# Artemis-Flex-Femto.net
KiCad netlist of a schematic drawn in EAGLE
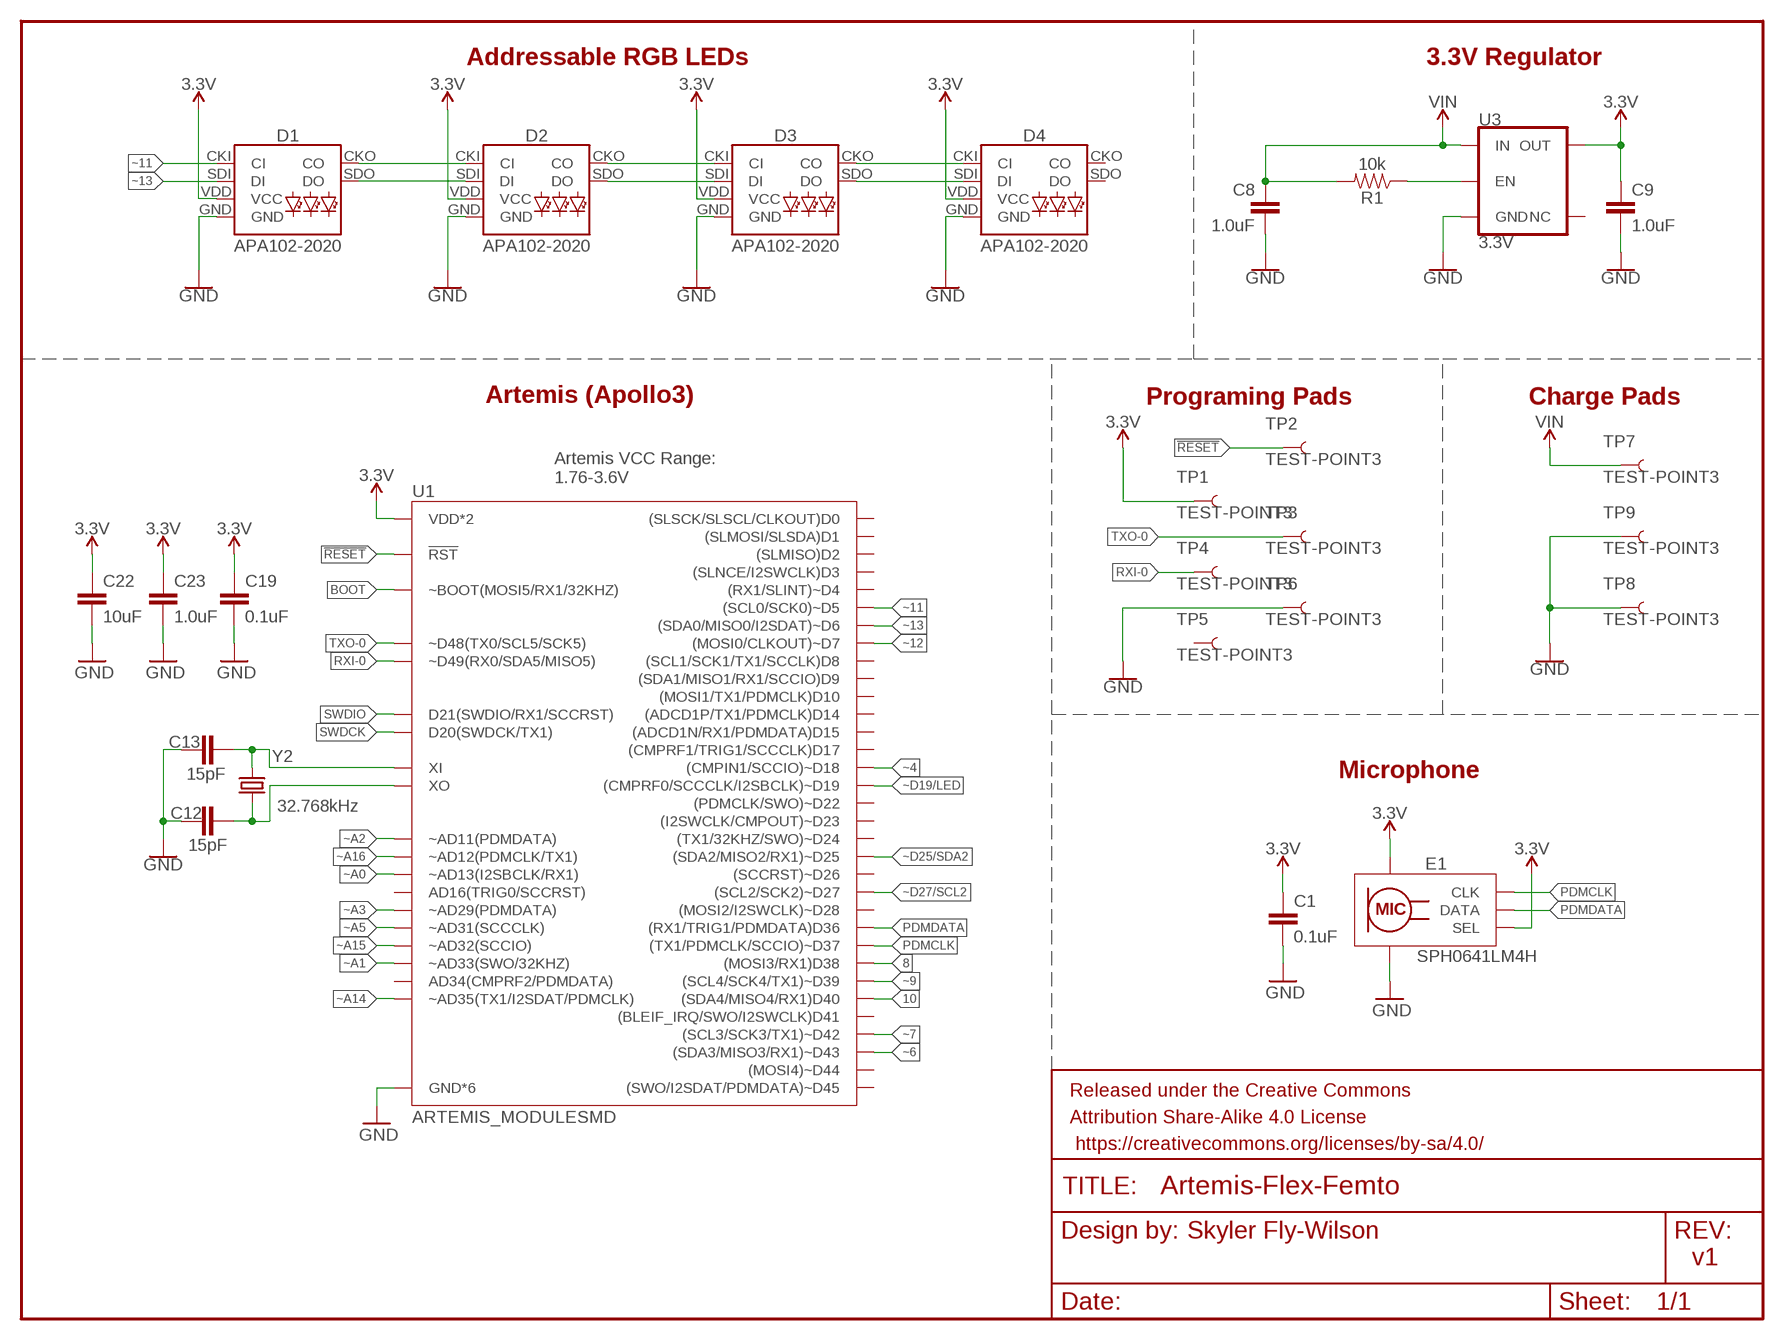
[diagram p0: schematic, sheet 1]

(export (version "E")
  (design (tool "Eeschema 10.0.6"))
  (components
    (comp (ref "C1")
      (value "0.1uF")
      (footprint "eagle-import:0402-TIGHT")
      (libsource (lib "eagle-import") (part "0.1UF-0402T-16V-10%"))
    )
    (comp (ref "C8")
      (value "1.0uF")
      (footprint "eagle-import:0402-TIGHT")
      (libsource (lib "eagle-import") (part "1.0UF-0402T-16V-10%"))
    )
    (comp (ref "C9")
      (value "1.0uF")
      (footprint "eagle-import:0402-TIGHT")
      (libsource (lib "eagle-import") (part "1.0UF-0402T-16V-10%"))
    )
    (comp (ref "C12")
      (value "15pF")
      (footprint "eagle-import:0603")
      (libsource (lib "eagle-import") (part "15PF-0603-50V-5%"))
    )
    (comp (ref "C13")
      (value "15pF")
      (footprint "eagle-import:0603")
      (libsource (lib "eagle-import") (part "15PF-0603-50V-5%"))
    )
    (comp (ref "C19")
      (value "0.1uF")
      (footprint "eagle-import:0402-TIGHT")
      (libsource (lib "eagle-import") (part "0.1UF-0402T-16V-10%"))
    )
    (comp (ref "C22")
      (value "10uF")
      (footprint "eagle-import:0603")
      (libsource (lib "eagle-import") (part "10UF-0603-6.3V-20%"))
    )
    (comp (ref "C23")
      (value "1.0uF")
      (footprint "eagle-import:0402-TIGHT")
      (libsource (lib "eagle-import") (part "1.0UF-0402T-16V-10%"))
    )
    (comp (ref "D1")
      (value "APA102-2020")
      (footprint "eagle-import:APA102-2020")
      (libsource (lib "eagle-import") (part "APA102-2020"))
    )
    (comp (ref "D2")
      (value "APA102-2020")
      (footprint "eagle-import:APA102-2020")
      (libsource (lib "eagle-import") (part "APA102-2020"))
    )
    (comp (ref "D3")
      (value "APA102-2020")
      (footprint "eagle-import:APA102-2020")
      (libsource (lib "eagle-import") (part "APA102-2020"))
    )
    (comp (ref "D4")
      (value "APA102-2020")
      (footprint "eagle-import:APA102-2020")
      (libsource (lib "eagle-import") (part "APA102-2020"))
    )
    (comp (ref "E1")
      (value "SPH0641LM4H")
      (footprint "eagle-import:SPH0641LM4H-1_MICROPHONE")
      (libsource (lib "eagle-import") (part "SPH0641LM4H-1_MICROPHONE"))
    )
    (comp (ref "FRAME1")
      (value "FRAME-LETTER")
      (footprint "eagle-import:CREATIVE_COMMONS")
      (libsource (lib "eagle-import") (part "FRAME-LETTER"))
    )
    (comp (ref "R1")
      (value "10k")
      (footprint "eagle-import:0603")
      (libsource (lib "eagle-import") (part "10KOHM-0603-1/10W-1%"))
    )
    (comp (ref "TP1")
      (value "TEST-POINT3")
      (footprint "eagle-import:PAD.03X.03")
      (libsource (lib "eagle-import") (part "TEST-POINT3"))
    )
    (comp (ref "TP2")
      (value "TEST-POINT3")
      (footprint "eagle-import:PAD.03X.03")
      (libsource (lib "eagle-import") (part "TEST-POINT3"))
    )
    (comp (ref "TP3")
      (value "TEST-POINT3")
      (footprint "eagle-import:PAD.03X.03")
      (libsource (lib "eagle-import") (part "TEST-POINT3"))
    )
    (comp (ref "TP4")
      (value "TEST-POINT3")
      (footprint "eagle-import:PAD.03X.03")
      (libsource (lib "eagle-import") (part "TEST-POINT3"))
    )
    (comp (ref "TP5")
      (value "TEST-POINT3")
      (footprint "eagle-import:PAD.03X.03")
      (libsource (lib "eagle-import") (part "TEST-POINT3"))
    )
    (comp (ref "TP6")
      (value "TEST-POINT3")
      (footprint "eagle-import:PAD.03X.03")
      (libsource (lib "eagle-import") (part "TEST-POINT3"))
    )
    (comp (ref "TP7")
      (value "TEST-POINT3")
      (footprint "eagle-import:PAD.03X.03")
      (libsource (lib "eagle-import") (part "TEST-POINT3"))
    )
    (comp (ref "TP8")
      (value "TEST-POINT3")
      (footprint "eagle-import:PAD.03X.03")
      (libsource (lib "eagle-import") (part "TEST-POINT3"))
    )
    (comp (ref "TP9")
      (value "TEST-POINT3")
      (footprint "eagle-import:PAD.03X.03")
      (libsource (lib "eagle-import") (part "TEST-POINT3"))
    )
    (comp (ref "U1")
      (value "ARTEMIS_MODULESMD")
      (footprint "eagle-import:ARTEMIS_FP")
      (libsource (lib "eagle-import") (part "ARTEMIS_MODULESMD"))
    )
    (comp (ref "U3")
      (value "3.3V")
      (footprint "eagle-import:SOT23-5")
      (libsource (lib "eagle-import") (part "V_REG_AP2112K-3.3V"))
    )
    (comp (ref "Y2")
      (value "32.768kHz")
      (footprint "eagle-import:CRYSTAL-SMD-3.2X1.5MM")
      (libsource (lib "eagle-import") (part "CRYSTAL-32.768KHZSMD-3.2X1.5"))
    )
  )
  (nets
    (net (code "1") (name "/~{4}") (class "Default")
      (node (ref "U1") (pin "~D18") (pinfunction "(CMPIN1/SCCIO)~{D18}_~D18") (pintype "bidirectional"))
    )
    (net (code "2") (name "/~{6}") (class "Default")
      (node (ref "U1") (pin "~D43") (pinfunction "(SDA3/MISO3/RX1)~{D43}_~D43") (pintype "bidirectional"))
    )
    (net (code "3") (name "/~{7}") (class "Default")
      (node (ref "U1") (pin "~D42") (pinfunction "(SCL3/SCK3/TX1)~{D42}_~D42") (pintype "bidirectional"))
    )
    (net (code "4") (name "/~{9}") (class "Default")
      (node (ref "U1") (pin "~D39") (pinfunction "(SCL4/SCK4/TX1)~{D39}_~D39") (pintype "bidirectional"))
    )
    (net (code "5") (name "/~{11}") (class "Default")
      (node (ref "U1") (pin "~D5") (pinfunction "(SCL0/SCK0)~{D5}_~D5") (pintype "bidirectional"))
    )
    (net (code "6") (name "/~{12}") (class "Default")
      (node (ref "U1") (pin "D7") (pinfunction "(MOSI0/CLKOUT)~{D7}_D7") (pintype "bidirectional"))
    )
    (net (code "7") (name "/~{13}") (class "Default")
      (node (ref "U1") (pin "~D6") (pinfunction "(SDA0/MISO0/I2SDAT)~{D6}_~D6") (pintype "bidirectional"))
    )
    (net (code "8") (name "/~{A0}") (class "Default")
      (node (ref "U1") (pin "~AD13") (pinfunction "~{AD13(I2SBCLK/RX1})_~AD13") (pintype "bidirectional"))
    )
    (net (code "9") (name "/~{A1}") (class "Default")
      (node (ref "U1") (pin "~AD33/SWO") (pinfunction "~{AD33(SWO/32KHZ})_~AD33/SWO") (pintype "bidirectional"))
    )
    (net (code "10") (name "/~{A2}") (class "Default")
      (node (ref "U1") (pin "~AD11") (pinfunction "~{AD11(PDMDATA})_~AD11") (pintype "bidirectional"))
    )
    (net (code "11") (name "/~{A3}") (class "Default")
      (node (ref "U1") (pin "~AD29") (pinfunction "~{AD29(PDMDATA})_~AD29") (pintype "bidirectional"))
    )
    (net (code "12") (name "/~{A5}") (class "Default")
      (node (ref "U1") (pin "~AD31") (pinfunction "~{AD31(SCCCLK})_~AD31") (pintype "bidirectional"))
    )
    (net (code "13") (name "/~{A14}") (class "Default")
      (node (ref "U1") (pin "~AD35") (pinfunction "~{AD35(TX1/I2SDAT/PDMCLK})_~AD35") (pintype "bidirectional"))
    )
    (net (code "14") (name "/~{A15}") (class "Default")
      (node (ref "U1") (pin "~AD32") (pinfunction "~{AD32(SCCIO})_~AD32") (pintype "bidirectional"))
    )
    (net (code "15") (name "/~{A16}") (class "Default")
      (node (ref "U1") (pin "~AD12") (pinfunction "~{AD12(PDMCLK/TX1})_~AD12") (pintype "bidirectional"))
    )
    (net (code "16") (name "/~{D19{slash}LED}") (class "Default")
      (node (ref "U1") (pin "~D19") (pinfunction "(CMPRF0/SCCCLK/I2SBCLK)~{D19}_~D19") (pintype "bidirectional"))
    )
    (net (code "17") (name "/~{D25{slash}SDA2}") (class "Default")
      (node (ref "U1") (pin "~D25") (pinfunction "(SDA2/MISO2/RX1)~{D25}_~D25") (pintype "bidirectional"))
    )
    (net (code "18") (name "/~{D27{slash}SCL2}") (class "Default")
      (node (ref "U1") (pin "~D27") (pinfunction "(SCL2/SCK2)~{D27}_~D27") (pintype "bidirectional"))
    )
    (net (code "19") (name "/~{RESET}") (class "Default")
      (node (ref "U1") (pin "~RST") (pinfunction "~{RST}_~RST") (pintype "bidirectional"))
    )
    (net (code "20") (name "3.3V") (class "Default")
      (node (ref "C1") (pin "1") (pinfunction "1_1") (pintype "passive"))
      (node (ref "C19") (pin "2") (pinfunction "2_2") (pintype "passive"))
      (node (ref "C22") (pin "1") (pinfunction "1_1") (pintype "passive"))
      (node (ref "C23") (pin "1") (pinfunction "1_1") (pintype "passive"))
      (node (ref "C9") (pin "1") (pinfunction "1_1") (pintype "passive"))
      (node (ref "D1") (pin "VDD") (pinfunction "VCC_VDD") (pintype "bidirectional"))
      (node (ref "D2") (pin "VDD") (pinfunction "VCC_VDD") (pintype "bidirectional"))
      (node (ref "D3") (pin "VDD") (pinfunction "VCC_VDD") (pintype "bidirectional"))
      (node (ref "D4") (pin "VDD") (pinfunction "VCC_VDD") (pintype "bidirectional"))
      (node (ref "E1") (pin "2") (pinfunction "SEL_2") (pintype "input"))
      (node (ref "E1") (pin "5") (pinfunction "VDD_5") (pintype "power_in"))
      (node (ref "TP1") (pin "P$1") (pinfunction "1_P$1") (pintype "bidirectional"))
      (node (ref "U1") (pin "VDD@36") (pinfunction "VDD*2_VDD@36") (pintype "bidirectional"))
      (node (ref "U1") (pin "VDD@37") (pinfunction "VDD*2_VDD@37") (pintype "bidirectional"))
      (node (ref "U3") (pin "5") (pinfunction "OUT_5") (pintype "passive"))
    )
    (net (code "21") (name "8") (class "Default")
      (node (ref "U1") (pin "D38") (pinfunction "(MOSI3/RX1)D38_D38") (pintype "bidirectional"))
    )
    (net (code "22") (name "10") (class "Default")
      (node (ref "U1") (pin "D40") (pinfunction "(SDA4/MISO4/RX1)D40_D40") (pintype "bidirectional"))
    )
    (net (code "23") (name "BOOT") (class "Default")
      (node (ref "U1") (pin "BOOT") (pinfunction "~{BOOT(MOSI5/RX1/32KHZ})_BOOT") (pintype "bidirectional"))
    )
    (net (code "24") (name "GND") (class "Default")
      (node (ref "C1") (pin "2") (pinfunction "2_2") (pintype "passive"))
      (node (ref "C12") (pin "1") (pinfunction "1_1") (pintype "passive"))
      (node (ref "C13") (pin "1") (pinfunction "1_1") (pintype "passive"))
      (node (ref "C19") (pin "1") (pinfunction "1_1") (pintype "passive"))
      (node (ref "C22") (pin "2") (pinfunction "2_2") (pintype "passive"))
      (node (ref "C23") (pin "2") (pinfunction "2_2") (pintype "passive"))
      (node (ref "C8") (pin "2") (pinfunction "2_2") (pintype "passive"))
      (node (ref "C9") (pin "2") (pinfunction "2_2") (pintype "passive"))
      (node (ref "D1") (pin "GND") (pinfunction "GND_GND") (pintype "bidirectional"))
      (node (ref "D2") (pin "GND") (pinfunction "GND_GND") (pintype "bidirectional"))
      (node (ref "D3") (pin "GND") (pinfunction "GND_GND") (pintype "bidirectional"))
      (node (ref "D4") (pin "GND") (pinfunction "GND_GND") (pintype "bidirectional"))
      (node (ref "E1") (pin "3") (pinfunction "GND_3") (pintype "power_in"))
      (node (ref "E1") (pin "6") (pinfunction "GND_6") (pintype "power_in"))
      (node (ref "E1") (pin "7") (pinfunction "GND_7") (pintype "power_in"))
      (node (ref "E1") (pin "8") (pinfunction "GND_8") (pintype "power_in"))
      (node (ref "TP6") (pin "P$1") (pinfunction "1_P$1") (pintype "bidirectional"))
      (node (ref "TP8") (pin "P$1") (pinfunction "1_P$1") (pintype "bidirectional"))
      (node (ref "TP9") (pin "P$1") (pinfunction "1_P$1") (pintype "bidirectional"))
      (node (ref "U1") (pin "GND@1") (pinfunction "GND*6_GND@1") (pintype "bidirectional"))
      (node (ref "U1") (pin "GND@22") (pinfunction "GND*6_GND@22") (pintype "bidirectional"))
      (node (ref "U1") (pin "GND@38") (pinfunction "GND*6_GND@38") (pintype "bidirectional"))
      (node (ref "U1") (pin "GND@39") (pinfunction "GND*6_GND@39") (pintype "bidirectional"))
      (node (ref "U1") (pin "GND@47") (pinfunction "GND*6_GND@47") (pintype "bidirectional"))
      (node (ref "U1") (pin "GND@59") (pinfunction "GND*6_GND@59") (pintype "bidirectional"))
      (node (ref "U3") (pin "2") (pinfunction "GND_2") (pintype "input"))
    )
    (net (code "25") (name "Net-(D1-CO)") (class "Default")
      (node (ref "D1") (pin "CKO") (pinfunction "CO_CKO") (pintype "bidirectional"))
      (node (ref "D2") (pin "CKI") (pinfunction "CI_CKI") (pintype "bidirectional"))
    )
    (net (code "26") (name "Net-(D1-DO)") (class "Default")
      (node (ref "D1") (pin "SDO") (pinfunction "DO_SDO") (pintype "bidirectional"))
      (node (ref "D2") (pin "SDI") (pinfunction "DI_SDI") (pintype "bidirectional"))
    )
    (net (code "27") (name "Net-(D2-CO)") (class "Default")
      (node (ref "D2") (pin "CKO") (pinfunction "CO_CKO") (pintype "bidirectional"))
      (node (ref "D3") (pin "CKI") (pinfunction "CI_CKI") (pintype "bidirectional"))
    )
    (net (code "28") (name "Net-(D2-DO)") (class "Default")
      (node (ref "D2") (pin "SDO") (pinfunction "DO_SDO") (pintype "bidirectional"))
      (node (ref "D3") (pin "SDI") (pinfunction "DI_SDI") (pintype "bidirectional"))
    )
    (net (code "29") (name "Net-(D3-CO)") (class "Default")
      (node (ref "D3") (pin "CKO") (pinfunction "CO_CKO") (pintype "bidirectional"))
      (node (ref "D4") (pin "CKI") (pinfunction "CI_CKI") (pintype "bidirectional"))
    )
    (net (code "30") (name "Net-(D3-DO)") (class "Default")
      (node (ref "D3") (pin "SDO") (pinfunction "DO_SDO") (pintype "bidirectional"))
      (node (ref "D4") (pin "SDI") (pinfunction "DI_SDI") (pintype "bidirectional"))
    )
    (net (code "31") (name "Net-(U3-EN)") (class "Default")
      (node (ref "R1") (pin "1") (pinfunction "1_1") (pintype "passive"))
      (node (ref "U3") (pin "3") (pinfunction "EN_3") (pintype "input"))
    )
    (net (code "32") (name "Net-(Y2-1)") (class "Default")
      (node (ref "C13") (pin "2") (pinfunction "2_2") (pintype "passive"))
      (node (ref "U1") (pin "XI") (pinfunction "XI_XI") (pintype "bidirectional"))
      (node (ref "Y2") (pin "P$1") (pinfunction "1_P$1") (pintype "passive"))
    )
    (net (code "33") (name "Net-(Y2-2)") (class "Default")
      (node (ref "C12") (pin "2") (pinfunction "2_2") (pintype "passive"))
      (node (ref "U1") (pin "XO") (pinfunction "XO_XO") (pintype "bidirectional"))
      (node (ref "Y2") (pin "P$2") (pinfunction "2_P$2") (pintype "passive"))
    )
    (net (code "34") (name "PDMCLK") (class "Default")
      (node (ref "E1") (pin "4") (pinfunction "CLK_4") (pintype "input"))
      (node (ref "U1") (pin "~D37") (pinfunction "(TX1/PDMCLK/SCCIO)~{D37}_~D37") (pintype "bidirectional"))
    )
    (net (code "35") (name "PDMDATA") (class "Default")
      (node (ref "E1") (pin "1") (pinfunction "DATA_1") (pintype "output"))
      (node (ref "U1") (pin "D36") (pinfunction "(RX1/TRIG1/PDMDATA)D36_D36") (pintype "bidirectional"))
    )
    (net (code "36") (name "RXI-0") (class "Default")
      (node (ref "U1") (pin "RXI-0") (pinfunction "~{D49(RX0/SDA5/MISO5})_RXI-0") (pintype "bidirectional"))
    )
    (net (code "37") (name "SWDCK") (class "Default")
      (node (ref "U1") (pin "SWDCK") (pinfunction "D20(SWDCK/TX1)_SWDCK") (pintype "bidirectional"))
    )
    (net (code "38") (name "SWDIO") (class "Default")
      (node (ref "U1") (pin "SWDIO") (pinfunction "D21(SWDIO/RX1/SCCRST)_SWDIO") (pintype "bidirectional"))
    )
    (net (code "39") (name "TXO-0") (class "Default")
      (node (ref "U1") (pin "TXO-0") (pinfunction "~{D48(TX0/SCL5/SCK5})_TXO-0") (pintype "bidirectional"))
    )
    (net (code "40") (name "VIN") (class "Default")
      (node (ref "C8") (pin "1") (pinfunction "1_1") (pintype "passive"))
      (node (ref "R1") (pin "2") (pinfunction "2_2") (pintype "passive"))
      (node (ref "TP7") (pin "P$1") (pinfunction "1_P$1") (pintype "bidirectional"))
      (node (ref "U3") (pin "1") (pinfunction "IN_1") (pintype "input"))
    )
    (net (code "41") (name "unconnected-(D1-CI-PadCKI)") (class "Default")
      (node (ref "D1") (pin "CKI") (pinfunction "CI_CKI") (pintype "bidirectional"))
    )
    (net (code "42") (name "unconnected-(D1-DI-PadSDI)") (class "Default")
      (node (ref "D1") (pin "SDI") (pinfunction "DI_SDI") (pintype "bidirectional"))
    )
    (net (code "43") (name "unconnected-(D4-CO-PadCKO)") (class "Default")
      (node (ref "D4") (pin "CKO") (pinfunction "CO_CKO") (pintype "bidirectional"))
    )
    (net (code "44") (name "unconnected-(D4-DO-PadSDO)") (class "Default")
      (node (ref "D4") (pin "SDO") (pinfunction "DO_SDO") (pintype "bidirectional"))
    )
    (net (code "45") (name "unconnected-(TP2-1-PadP$1)") (class "Default")
      (node (ref "TP2") (pin "P$1") (pinfunction "1_P$1") (pintype "bidirectional"))
    )
    (net (code "46") (name "unconnected-(TP3-1-PadP$1)") (class "Default")
      (node (ref "TP3") (pin "P$1") (pinfunction "1_P$1") (pintype "bidirectional"))
    )
    (net (code "47") (name "unconnected-(TP4-1-PadP$1)") (class "Default")
      (node (ref "TP4") (pin "P$1") (pinfunction "1_P$1") (pintype "bidirectional"))
    )
    (net (code "48") (name "unconnected-(TP5-1-PadP$1)") (class "Default")
      (node (ref "TP5") (pin "P$1") (pinfunction "1_P$1") (pintype "bidirectional"))
    )
    (net (code "49") (name "unconnected-(U1-(ADCD1N{slash}RX1{slash}PDMDATA)D15-PadD15)") (class "Default")
      (node (ref "U1") (pin "D15") (pinfunction "(ADCD1N/RX1/PDMDATA)D15_D15") (pintype "bidirectional"))
    )
    (net (code "50") (name "unconnected-(U1-(ADCD1P{slash}TX1{slash}PDMCLK)D14-PadD14)") (class "Default")
      (node (ref "U1") (pin "D14") (pinfunction "(ADCD1P/TX1/PDMCLK)D14_D14") (pintype "bidirectional"))
    )
    (net (code "51") (name "unconnected-(U1-(BLEIF_IRQ{slash}SWO{slash}I2SWCLK)D41-PadD41)") (class "Default")
      (node (ref "U1") (pin "D41") (pinfunction "(BLEIF_IRQ/SWO/I2SWCLK)D41_D41") (pintype "bidirectional"))
    )
    (net (code "52") (name "unconnected-(U1-(CMPRF1{slash}TRIG1{slash}SCCCLK)D17-PadD17)") (class "Default")
      (node (ref "U1") (pin "D17") (pinfunction "(CMPRF1/TRIG1/SCCCLK)D17_D17") (pintype "bidirectional"))
    )
    (net (code "53") (name "unconnected-(U1-(I2SWCLK{slash}CMPOUT)~{D23}-Pad~D23)") (class "Default")
      (node (ref "U1") (pin "~D23") (pinfunction "(I2SWCLK/CMPOUT)~{D23}_~D23") (pintype "bidirectional"))
    )
    (net (code "54") (name "unconnected-(U1-(MOSI1{slash}TX1{slash}PDMCLK)D10-PadD10)") (class "Default")
      (node (ref "U1") (pin "D10") (pinfunction "(MOSI1/TX1/PDMCLK)D10_D10") (pintype "bidirectional"))
    )
    (net (code "55") (name "unconnected-(U1-(MOSI2{slash}I2SWCLK)~{D28}-Pad~D28)") (class "Default")
      (node (ref "U1") (pin "~D28") (pinfunction "(MOSI2/I2SWCLK)~{D28}_~D28") (pintype "bidirectional"))
    )
    (net (code "56") (name "unconnected-(U1-(MOSI4)~{D44}-Pad~D44)") (class "Default")
      (node (ref "U1") (pin "~D44") (pinfunction "(MOSI4)~{D44}_~D44") (pintype "bidirectional"))
    )
    (net (code "57") (name "unconnected-(U1-(PDMCLK{slash}SWO)~{D22}-Pad~D22)") (class "Default")
      (node (ref "U1") (pin "~D22") (pinfunction "(PDMCLK/SWO)~{D22}_~D22") (pintype "bidirectional"))
    )
    (net (code "58") (name "unconnected-(U1-(RX1{slash}SLINT)~{D4}-Pad~D4)") (class "Default")
      (node (ref "U1") (pin "~D4") (pinfunction "(RX1/SLINT)~{D4}_~D4") (pintype "bidirectional"))
    )
    (net (code "59") (name "unconnected-(U1-(SCCRST)~{D26}-Pad~D26)") (class "Default")
      (node (ref "U1") (pin "~D26") (pinfunction "(SCCRST)~{D26}_~D26") (pintype "bidirectional"))
    )
    (net (code "60") (name "unconnected-(U1-(SCL1{slash}SCK1{slash}TX1{slash}SCCLK)D8-PadD8)") (class "Default")
      (node (ref "U1") (pin "D8") (pinfunction "(SCL1/SCK1/TX1/SCCLK)D8_D8") (pintype "bidirectional"))
    )
    (net (code "61") (name "unconnected-(U1-(SDA1{slash}MISO1{slash}RX1{slash}SCCIO)D9-PadD9)") (class "Default")
      (node (ref "U1") (pin "D9") (pinfunction "(SDA1/MISO1/RX1/SCCIO)D9_D9") (pintype "bidirectional"))
    )
    (net (code "62") (name "unconnected-(U1-(SLMISO)D2-PadD2)") (class "Default")
      (node (ref "U1") (pin "D2") (pinfunction "(SLMISO)D2_D2") (pintype "bidirectional"))
    )
    (net (code "63") (name "unconnected-(U1-(SLMOSI{slash}SLSDA)D1-PadD1)") (class "Default")
      (node (ref "U1") (pin "D1") (pinfunction "(SLMOSI/SLSDA)D1_D1") (pintype "bidirectional"))
    )
    (net (code "64") (name "unconnected-(U1-(SLNCE{slash}I2SWCLK)D3-PadD3)") (class "Default")
      (node (ref "U1") (pin "D3") (pinfunction "(SLNCE/I2SWCLK)D3_D3") (pintype "bidirectional"))
    )
    (net (code "65") (name "unconnected-(U1-(SLSCK{slash}SLSCL{slash}CLKOUT)D0-PadD0)") (class "Default")
      (node (ref "U1") (pin "D0") (pinfunction "(SLSCK/SLSCL/CLKOUT)D0_D0") (pintype "bidirectional"))
    )
    (net (code "66") (name "unconnected-(U1-(SWO{slash}I2SDAT{slash}PDMDATA)~{D45}-Pad~D45)") (class "Default")
      (node (ref "U1") (pin "~D45") (pinfunction "(SWO/I2SDAT/PDMDATA)~{D45}_~D45") (pintype "bidirectional"))
    )
    (net (code "67") (name "unconnected-(U1-(TX1{slash}32KHZ{slash}SWO)~{D24}-Pad~D24)") (class "Default")
      (node (ref "U1") (pin "~D24") (pinfunction "(TX1/32KHZ/SWO)~{D24}_~D24") (pintype "bidirectional"))
    )
    (net (code "68") (name "unconnected-(U1-AD16(TRIG0{slash}SCCRST)-PadAD16)") (class "Default")
      (node (ref "U1") (pin "AD16") (pinfunction "AD16(TRIG0/SCCRST)_AD16") (pintype "bidirectional"))
    )
    (net (code "69") (name "unconnected-(U1-AD34(CMPRF2{slash}PDMDATA)-PadAD34)") (class "Default")
      (node (ref "U1") (pin "AD34") (pinfunction "AD34(CMPRF2/PDMDATA)_AD34") (pintype "bidirectional"))
    )
    (net (code "70") (name "unconnected-(U3-NC-Pad4)") (class "Default")
      (node (ref "U3") (pin "4") (pinfunction "NC_4") (pintype "no_connect"))
    )
  )
)
